# RGB-LED-dimmer.net
KiCad netlist of a schematic drawn in EAGLE
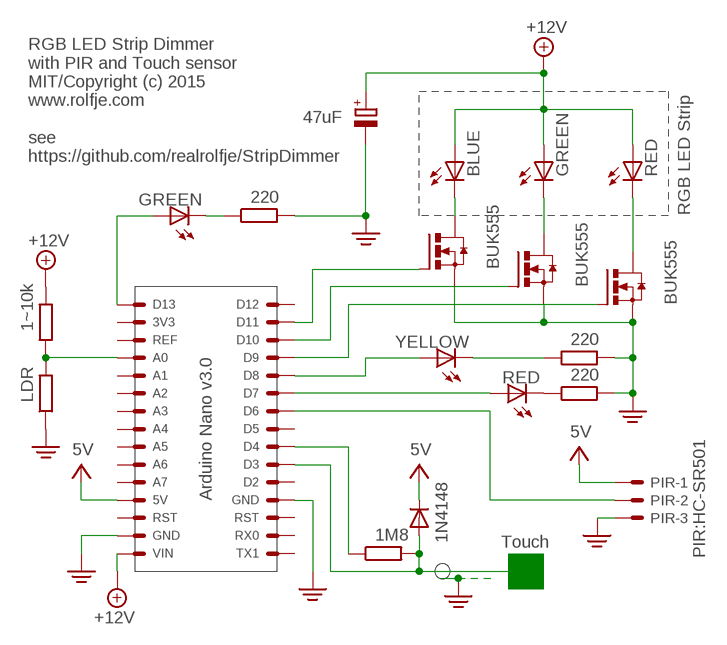
[diagram p0: schematic, sheet 1]

(export (version "E")
  (design (tool "Eeschema 10.0.6"))
  (components
    (comp (ref "A")
      (value "C-GRID-15-70543")
      (footprint "eagle-import:70543-15")
      (libsource (lib "eagle-import") (part "C-GRID-15-70543"))
    )
    (comp (ref "B")
      (value "C-GRID-15-70543")
      (footprint "eagle-import:70543-15")
      (libsource (lib "eagle-import") (part "C-GRID-15-70543"))
    )
    (comp (ref "BLUE")
      (value "LED5MM")
      (footprint "eagle-import:LED5MM")
      (libsource (lib "eagle-import") (part "LED5MM"))
    )
    (comp (ref "C1")
      (value "47uF")
      (footprint "eagle-import:E2,5-5")
      (libsource (lib "eagle-import") (part "CPOL-EUE2.5-5"))
    )
    (comp (ref "D1")
      (value "1N4148")
      (footprint "eagle-import:DO35-7")
      (libsource (lib "eagle-import") (part "1N4148DO35-7"))
    )
    (comp (ref "GREEN")
      (value "LED5MM")
      (footprint "eagle-import:LED5MM")
      (libsource (lib "eagle-import") (part "LED5MM"))
    )
    (comp (ref "LDR")
      (value "LDR")
      (footprint "eagle-import:0204_7")
      (libsource (lib "eagle-import") (part "R-EU_0204/7"))
    )
    (comp (ref "LED1")
      (value "YELLOW")
      (footprint "eagle-import:LED5MM")
      (libsource (lib "eagle-import") (part "LED5MM"))
    )
    (comp (ref "LED2")
      (value "RED")
      (footprint "eagle-import:LED5MM")
      (libsource (lib "eagle-import") (part "LED5MM"))
    )
    (comp (ref "LED3")
      (value "GREEN")
      (footprint "eagle-import:LED5MM")
      (libsource (lib "eagle-import") (part "LED5MM"))
    )
    (comp (ref "PIR")
      (value "PIR:HC-SR501")
      (footprint "eagle-import:70543-03")
      (libsource (lib "eagle-import") (part "C-GRID-03-70543"))
    )
    (comp (ref "Q1")
      (value "BUK555")
      (footprint "eagle-import:TO262-V")
      (libsource (lib "eagle-import") (part "IRF3704L-V"))
    )
    (comp (ref "Q2")
      (value "BUK555")
      (footprint "eagle-import:TO262-V")
      (libsource (lib "eagle-import") (part "IRF3704L-V"))
    )
    (comp (ref "Q3")
      (value "BUK555")
      (footprint "eagle-import:TO262-V")
      (libsource (lib "eagle-import") (part "IRF3704L-V"))
    )
    (comp (ref "R1")
      (value "1M8")
      (footprint "eagle-import:0204_7")
      (libsource (lib "eagle-import") (part "R-EU_0204/7"))
    )
    (comp (ref "R2")
      (value "220")
      (footprint "eagle-import:0204_7")
      (libsource (lib "eagle-import") (part "R-EU_0204/7"))
    )
    (comp (ref "R3")
      (value "220")
      (footprint "eagle-import:0204_7")
      (libsource (lib "eagle-import") (part "R-EU_0204/7"))
    )
    (comp (ref "R4")
      (value "220")
      (footprint "eagle-import:0204_7")
      (libsource (lib "eagle-import") (part "R-EU_0204/7"))
    )
    (comp (ref "R5")
      (value "1~10k")
      (footprint "eagle-import:0204_7")
      (libsource (lib "eagle-import") (part "R-EU_0204/7"))
    )
    (comp (ref "RED")
      (value "LED5MM")
      (footprint "eagle-import:LED5MM")
      (libsource (lib "eagle-import") (part "LED5MM"))
    )
  )
  (nets
    (net (code "1") (name "+12V") (class "Default")
      (node (ref "A") (pin "15") (pinfunction "S_15") (pintype "passive"))
      (node (ref "BLUE") (pin "A") (pinfunction "A_A") (pintype "passive"))
      (node (ref "C1") (pin "+") (pinfunction "+_+") (pintype "passive"))
      (node (ref "GREEN") (pin "A") (pinfunction "A_A") (pintype "passive"))
      (node (ref "R5") (pin "2") (pinfunction "2_2") (pintype "passive"))
      (node (ref "RED") (pin "A") (pinfunction "A_A") (pintype "passive"))
    )
    (net (code "2") (name "5V") (class "Default")
      (node (ref "A") (pin "12") (pinfunction "S_12") (pintype "passive"))
      (node (ref "D1") (pin "C") (pinfunction "C_C") (pintype "passive"))
      (node (ref "PIR") (pin "1") (pinfunction "S_1") (pintype "passive"))
    )
    (net (code "3") (name "Net-(AA-S)") (class "Default")
      (node (ref "A") (pin "1") (pinfunction "S_1") (pintype "passive"))
      (node (ref "LED3") (pin "A") (pinfunction "A_A") (pintype "passive"))
    )
    (net (code "4") (name "Net-(AJ-S)") (class "Default")
      (node (ref "A") (pin "4") (pinfunction "S_4") (pintype "passive"))
      (node (ref "LDR") (pin "2") (pinfunction "2_2") (pintype "passive"))
      (node (ref "R5") (pin "1") (pinfunction "1_1") (pintype "passive"))
    )
    (net (code "5") (name "Net-(BB-S)") (class "Default")
      (node (ref "B") (pin "10") (pinfunction "S_10") (pintype "passive"))
      (node (ref "D1") (pin "A") (pinfunction "A_A") (pintype "passive"))
      (node (ref "R1") (pin "2") (pinfunction "2_2") (pintype "passive"))
    )
    (net (code "6") (name "Net-(BH-S)") (class "Default")
      (node (ref "B") (pin "2") (pinfunction "S_2") (pintype "passive"))
      (node (ref "Q3") (pin "1") (pinfunction "G_1") (pintype "passive"))
    )
    (net (code "7") (name "Net-(BI-S)") (class "Default")
      (node (ref "B") (pin "3") (pinfunction "S_3") (pintype "passive"))
      (node (ref "Q2") (pin "1") (pinfunction "G_1") (pintype "passive"))
    )
    (net (code "8") (name "Net-(BJ-S)") (class "Default")
      (node (ref "B") (pin "4") (pinfunction "S_4") (pintype "passive"))
      (node (ref "Q1") (pin "1") (pinfunction "G_1") (pintype "passive"))
    )
    (net (code "9") (name "Net-(BK-S)") (class "Default")
      (node (ref "B") (pin "5") (pinfunction "S_5") (pintype "passive"))
      (node (ref "LED1") (pin "A") (pinfunction "A_A") (pintype "passive"))
    )
    (net (code "10") (name "Net-(BL-S)") (class "Default")
      (node (ref "B") (pin "6") (pinfunction "S_6") (pintype "passive"))
      (node (ref "LED2") (pin "A") (pinfunction "A_A") (pintype "passive"))
    )
    (net (code "11") (name "Net-(BLUE-C)") (class "Default")
      (node (ref "BLUE") (pin "K") (pinfunction "C_K") (pintype "passive"))
      (node (ref "Q3") (pin "2") (pinfunction "D_2") (pintype "passive"))
    )
    (net (code "12") (name "Net-(BM-S)") (class "Default")
      (node (ref "B") (pin "7") (pinfunction "S_7") (pintype "passive"))
      (node (ref "PIR") (pin "2") (pinfunction "S_2") (pintype "passive"))
    )
    (net (code "13") (name "Net-(BO-S)") (class "Default")
      (node (ref "B") (pin "9") (pinfunction "S_9") (pintype "passive"))
      (node (ref "R1") (pin "1") (pinfunction "1_1") (pintype "passive"))
    )
    (net (code "14") (name "Net-(GREEN-C)") (class "Default")
      (node (ref "GREEN") (pin "K") (pinfunction "C_K") (pintype "passive"))
      (node (ref "Q2") (pin "2") (pinfunction "D_2") (pintype "passive"))
    )
    (net (code "15") (name "Net-(LED1-C)") (class "Default")
      (node (ref "LED1") (pin "K") (pinfunction "C_K") (pintype "passive"))
      (node (ref "R2") (pin "1") (pinfunction "1_1") (pintype "passive"))
    )
    (net (code "16") (name "Net-(LED2-C)") (class "Default")
      (node (ref "LED2") (pin "K") (pinfunction "C_K") (pintype "passive"))
      (node (ref "R3") (pin "1") (pinfunction "1_1") (pintype "passive"))
    )
    (net (code "17") (name "Net-(LED3-C)") (class "Default")
      (node (ref "LED3") (pin "K") (pinfunction "C_K") (pintype "passive"))
      (node (ref "R4") (pin "1") (pinfunction "1_1") (pintype "passive"))
    )
    (net (code "18") (name "Net-(Q1-D)") (class "Default")
      (node (ref "Q1") (pin "2") (pinfunction "D_2") (pintype "passive"))
      (node (ref "RED") (pin "K") (pinfunction "C_K") (pintype "passive"))
    )
    (net (code "19") (name "PE") (class "Default")
      (node (ref "A") (pin "14") (pinfunction "S_14") (pintype "passive"))
      (node (ref "B") (pin "12") (pinfunction "S_12") (pintype "passive"))
      (node (ref "C1") (pin "-") (pinfunction "-_-") (pintype "passive"))
      (node (ref "LDR") (pin "1") (pinfunction "1_1") (pintype "passive"))
      (node (ref "PIR") (pin "3") (pinfunction "S_3") (pintype "passive"))
      (node (ref "Q1") (pin "3") (pinfunction "S_3") (pintype "passive"))
      (node (ref "Q2") (pin "3") (pinfunction "S_3") (pintype "passive"))
      (node (ref "Q3") (pin "3") (pinfunction "S_3") (pintype "passive"))
      (node (ref "R2") (pin "2") (pinfunction "2_2") (pintype "passive"))
      (node (ref "R3") (pin "2") (pinfunction "2_2") (pintype "passive"))
      (node (ref "R4") (pin "2") (pinfunction "2_2") (pintype "passive"))
    )
    (net (code "20") (name "unconnected-(AB-S-Pad10)") (class "Default")
      (node (ref "A") (pin "10") (pinfunction "S_10") (pintype "passive"))
    )
    (net (code "21") (name "unconnected-(AC-S-Pad11)") (class "Default")
      (node (ref "A") (pin "11") (pinfunction "S_11") (pintype "passive"))
    )
    (net (code "22") (name "unconnected-(AE-S-Pad13)") (class "Default")
      (node (ref "A") (pin "13") (pinfunction "S_13") (pintype "passive"))
    )
    (net (code "23") (name "unconnected-(AH-S-Pad2)") (class "Default")
      (node (ref "A") (pin "2") (pinfunction "S_2") (pintype "passive"))
    )
    (net (code "24") (name "unconnected-(AI-S-Pad3)") (class "Default")
      (node (ref "A") (pin "3") (pinfunction "S_3") (pintype "passive"))
    )
    (net (code "25") (name "unconnected-(AK-S-Pad5)") (class "Default")
      (node (ref "A") (pin "5") (pinfunction "S_5") (pintype "passive"))
    )
    (net (code "26") (name "unconnected-(AL-S-Pad6)") (class "Default")
      (node (ref "A") (pin "6") (pinfunction "S_6") (pintype "passive"))
    )
    (net (code "27") (name "unconnected-(AM-S-Pad7)") (class "Default")
      (node (ref "A") (pin "7") (pinfunction "S_7") (pintype "passive"))
    )
    (net (code "28") (name "unconnected-(AN-S-Pad8)") (class "Default")
      (node (ref "A") (pin "8") (pinfunction "S_8") (pintype "passive"))
    )
    (net (code "29") (name "unconnected-(AO-S-Pad9)") (class "Default")
      (node (ref "A") (pin "9") (pinfunction "S_9") (pintype "passive"))
    )
    (net (code "30") (name "unconnected-(BA-S-Pad1)") (class "Default")
      (node (ref "B") (pin "1") (pinfunction "S_1") (pintype "passive"))
    )
    (net (code "31") (name "unconnected-(BC-S-Pad11)") (class "Default")
      (node (ref "B") (pin "11") (pinfunction "S_11") (pintype "passive"))
    )
    (net (code "32") (name "unconnected-(BE-S-Pad13)") (class "Default")
      (node (ref "B") (pin "13") (pinfunction "S_13") (pintype "passive"))
    )
    (net (code "33") (name "unconnected-(BF-S-Pad14)") (class "Default")
      (node (ref "B") (pin "14") (pinfunction "S_14") (pintype "passive"))
    )
    (net (code "34") (name "unconnected-(BG-S-Pad15)") (class "Default")
      (node (ref "B") (pin "15") (pinfunction "S_15") (pintype "passive"))
    )
    (net (code "35") (name "unconnected-(BN-S-Pad8)") (class "Default")
      (node (ref "B") (pin "8") (pinfunction "S_8") (pintype "passive"))
    )
  )
)
